# Power_Supply.net
KiCad netlist of a schematic drawn in Altium Designer
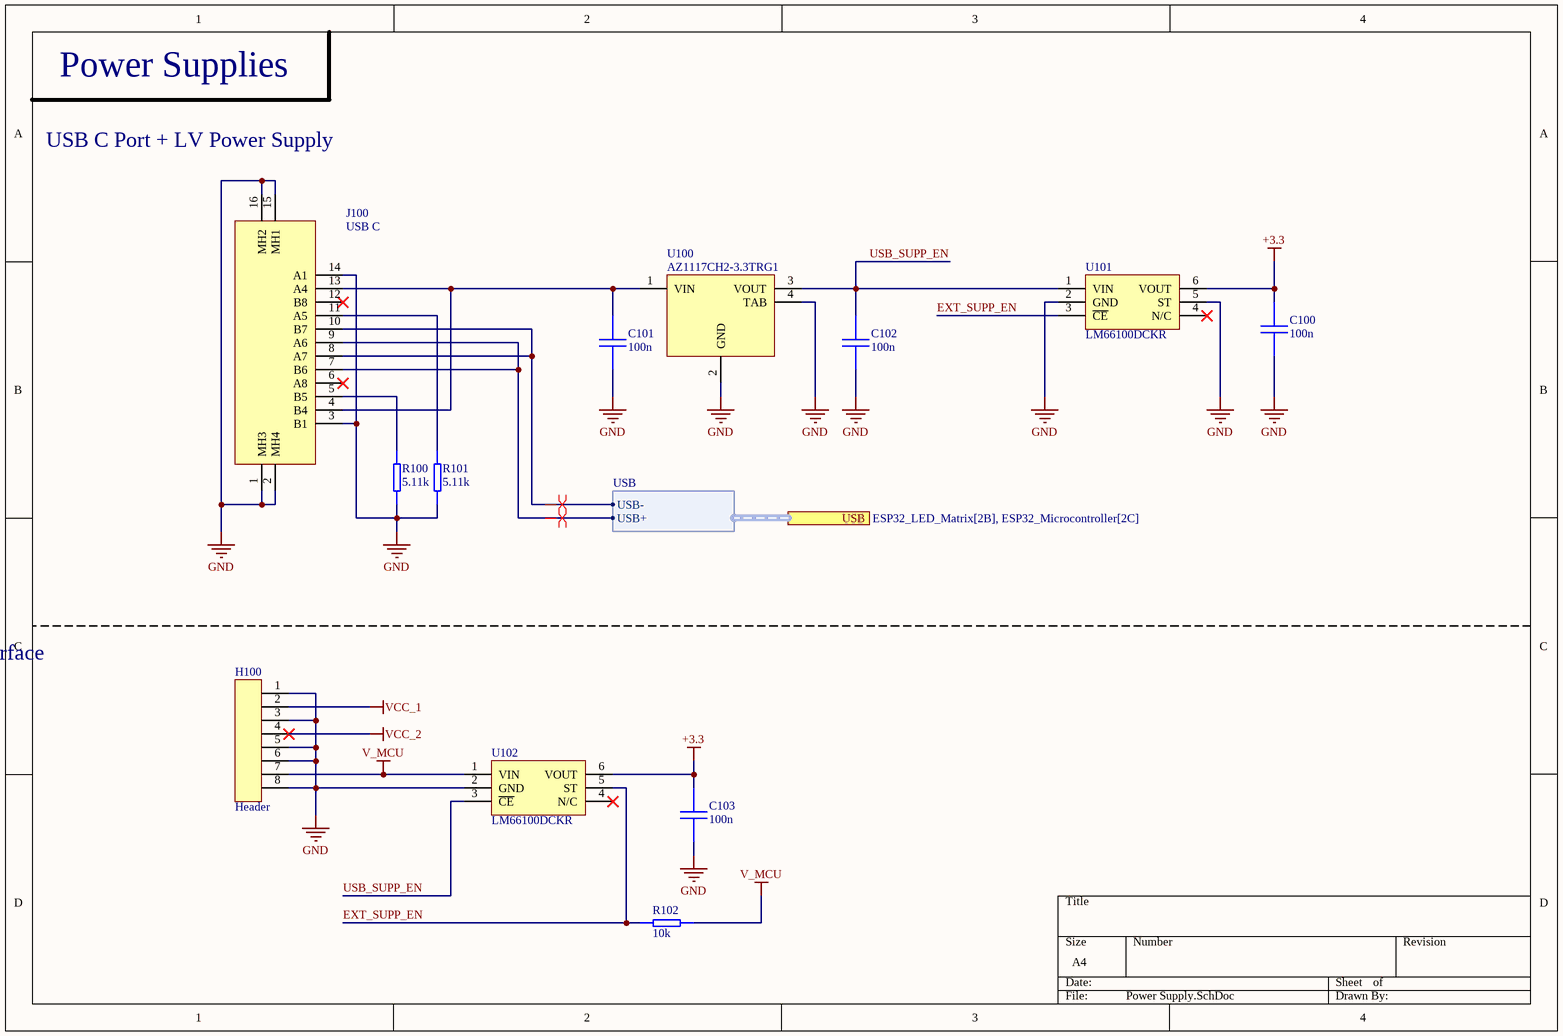
[diagram p0: Power Supply.SchDoc]

(export (version "E")
  (design (tool "Eeschema 10.0.6"))
  (components
    (comp (ref "C100")
      (value "100n")
      (footprint "IEEE_Workshop_Footprints:CAP0805")
      (description "Non Polarized Capacitor")
      (libsource (lib "HT2.2") (part "Capacitor - Non Polarized"))
    )
    (comp (ref "C101")
      (value "100n")
      (footprint "IEEE_Workshop_Footprints:CAP0805")
      (description "Non Polarized Capacitor")
      (libsource (lib "TD") (part "Capacitor - Non Polarized"))
    )
    (comp (ref "C102")
      (value "100n")
      (footprint "IEEE_Workshop_Footprints:CAP0805")
      (description "Non Polarized Capacitor")
      (libsource (lib "HT2.2") (part "Capacitor - Non Polarized"))
    )
    (comp (ref "C103")
      (value "100n")
      (footprint "IEEE_Workshop_Footprints:CAP0805")
      (description "Non Polarized Capacitor")
      (libsource (lib "HT2.2") (part "Capacitor - Non Polarized"))
    )
    (comp (ref "H100")
      (value "Header")
      (footprint "IEEE_Workshop_Footprints:Header_1X8")
      (description "8-Pin Header")
      (libsource (lib "TD") (part "8-Pin Header"))
    )
    (comp (ref "J100")
      (value "USB C")
      (footprint "IEEE_Workshop_Footprints:USB TYPE C 12 PIN")
      (libsource (lib "TD") (part "USB Type C Connector 12 Pin"))
    )
    (comp (ref "R100")
      (value "5.11k")
      (footprint "IEEE_Workshop_Footprints:RESC0805")
      (description "Resistor")
      (libsource (lib "HT2.2") (part "Resistor"))
    )
    (comp (ref "R101")
      (value "5.11k")
      (footprint "IEEE_Workshop_Footprints:RESC0805")
      (description "Resistor")
      (libsource (lib "HT2.2") (part "Resistor"))
    )
    (comp (ref "R102")
      (value "10k")
      (footprint "IEEE_Workshop_Footprints:RESC0805")
      (description "Resistor")
      (libsource (lib "TD") (part "Resistor"))
    )
    (comp (ref "U100")
      (value "AZ1117CH2-3.3TRG1")
      (footprint "IEEE_Workshop_Footprints:SOT223")
      (description "3.3V Linear Voltage Regulator")
      (libsource (lib "TD") (part "AZ1117CH2-3.3TRG1_1"))
    )
    (comp (ref "U101")
      (value "LM66100DCKR")
      (footprint "IEEE_Workshop_Footprints:SC70-6")
      (description "5.5-V, 1.5-A 79-mΩ, Low IQ Ideal Diode With Input Polarity Protection")
      (fields (field (name "MOUSER PART NUMBER") "595-LM66100DCKR"))
      (libsource (lib "TD") (part "LM66100DCKR"))
    )
    (comp (ref "U102")
      (value "LM66100DCKR")
      (footprint "IEEE_Workshop_Footprints:SC70-6")
      (description "5.5-V, 1.5-A 79-mΩ, Low IQ Ideal Diode With Input Polarity Protection")
      (fields (field (name "MOUSER PART NUMBER") "595-LM66100DCKR"))
      (libsource (lib "TD") (part "LM66100DCKR"))
    )
  )
  (nets
    (net (code "2") (name "+3.3") (class "Default")
      (node (ref "C100") (pin "1") (pintype "passive"))
      (node (ref "C103") (pin "1") (pintype "passive"))
      (node (ref "U101") (pin "6") (pinfunction "VOUT_6") (pintype "passive"))
      (node (ref "U102") (pin "6") (pinfunction "VOUT_6") (pintype "passive"))
    )
    (net (code "3") (name "/EXT_SUPP_EN") (class "Default")
      (node (ref "R102") (pin "1") (pintype "passive"))
      (node (ref "U101") (pin "3") (pinfunction "~{CE}_3") (pintype "passive"))
      (node (ref "U102") (pin "5") (pinfunction "ST_5") (pintype "passive"))
    )
    (net (code "4") (name "/USB_SUPP_EN") (class "Default")
      (node (ref "C102") (pin "1") (pintype "passive"))
      (node (ref "U100") (pin "3") (pinfunction "VOUT_3") (pintype "passive"))
      (node (ref "U101") (pin "1") (pinfunction "VIN_1") (pintype "passive"))
      (node (ref "U102") (pin "3") (pinfunction "~{CE}_3") (pintype "passive"))
    )
    (net (code "6") (name "GND") (class "Default")
      (node (ref "C100") (pin "2") (pintype "passive"))
      (node (ref "C101") (pin "2") (pintype "passive"))
      (node (ref "C102") (pin "2") (pintype "passive"))
      (node (ref "C103") (pin "2") (pintype "passive"))
      (node (ref "H100") (pin "1") (pintype "passive"))
      (node (ref "H100") (pin "3") (pintype "passive"))
      (node (ref "H100") (pin "5") (pintype "passive"))
      (node (ref "H100") (pin "6") (pintype "passive"))
      (node (ref "H100") (pin "8") (pintype "passive"))
      (node (ref "J100") (pin "1") (pinfunction "MH3_1") (pintype "passive"))
      (node (ref "J100") (pin "14") (pinfunction "A1_14") (pintype "passive"))
      (node (ref "J100") (pin "15") (pinfunction "MH1_15") (pintype "passive"))
      (node (ref "J100") (pin "16") (pinfunction "MH2_16") (pintype "passive"))
      (node (ref "J100") (pin "2") (pinfunction "MH4_2") (pintype "passive"))
      (node (ref "J100") (pin "3") (pinfunction "B1_3") (pintype "passive"))
      (node (ref "R100") (pin "1") (pintype "passive"))
      (node (ref "R101") (pin "1") (pintype "passive"))
      (node (ref "U100") (pin "2") (pinfunction "GND_2") (pintype "passive"))
      (node (ref "U100") (pin "4") (pinfunction "TAB_4") (pintype "passive"))
      (node (ref "U101") (pin "2") (pinfunction "GND_2") (pintype "passive"))
      (node (ref "U101") (pin "5") (pinfunction "ST_5") (pintype "passive"))
      (node (ref "U102") (pin "2") (pinfunction "GND_2") (pintype "passive"))
    )
    (net (code "7") (name "Net-(J100-A4)") (class "Default")
      (node (ref "C101") (pin "1") (pintype "passive"))
      (node (ref "J100") (pin "13") (pinfunction "A4_13") (pintype "passive"))
      (node (ref "J100") (pin "4") (pinfunction "B4_4") (pintype "passive"))
      (node (ref "U100") (pin "1") (pinfunction "VIN_1") (pintype "passive"))
    )
    (net (code "8") (name "Net-(J100-A5)") (class "Default")
      (node (ref "J100") (pin "11") (pinfunction "A5_11") (pintype "passive"))
      (node (ref "R101") (pin "2") (pintype "passive"))
    )
    (net (code "9") (name "Net-(J100-A6)") (class "Default")
      (node (ref "J100") (pin "7") (pinfunction "B6_7") (pintype "passive"))
      (node (ref "J100") (pin "9") (pinfunction "A6_9") (pintype "passive"))
    )
    (net (code "10") (name "Net-(J100-A7)") (class "Default")
      (node (ref "J100") (pin "10") (pinfunction "B7_10") (pintype "passive"))
      (node (ref "J100") (pin "8") (pinfunction "A7_8") (pintype "passive"))
    )
    (net (code "11") (name "Net-(J100-B5)") (class "Default")
      (node (ref "J100") (pin "5") (pinfunction "B5_5") (pintype "passive"))
      (node (ref "R100") (pin "2") (pintype "passive"))
    )
    (net (code "12") (name "VCC_1") (class "Default") (node (ref "H100") (pin "2") (pintype "passive")))
    (net (code "13") (name "VCC_2") (class "Default") (node (ref "H100") (pin "4") (pintype "passive")))
    (net (code "14") (name "V_MCU") (class "Default")
      (node (ref "H100") (pin "7") (pintype "passive"))
      (node (ref "R102") (pin "2") (pintype "passive"))
      (node (ref "U102") (pin "1") (pinfunction "VIN_1") (pintype "passive"))
    )
    (net (code "15") (name "unconnected-(J100-A8-Pad6)") (class "Default")
      (node (ref "J100") (pin "6") (pinfunction "A8_6") (pintype "passive+no_connect"))
    )
    (net (code "16") (name "unconnected-(J100-B8-Pad12)") (class "Default")
      (node (ref "J100") (pin "12") (pinfunction "B8_12") (pintype "passive+no_connect"))
    )
    (net (code "17") (name "unconnected-(U101-N{slash}C-Pad4)") (class "Default")
      (node (ref "U101") (pin "4") (pinfunction "N/C_4") (pintype "passive+no_connect"))
    )
    (net (code "18") (name "unconnected-(U102-N{slash}C-Pad4)") (class "Default")
      (node (ref "U102") (pin "4") (pinfunction "N/C_4") (pintype "passive+no_connect"))
    )
  )
)
